# I2C_ESP32_Module.net
KiCad netlist of a schematic drawn in Altium Designer
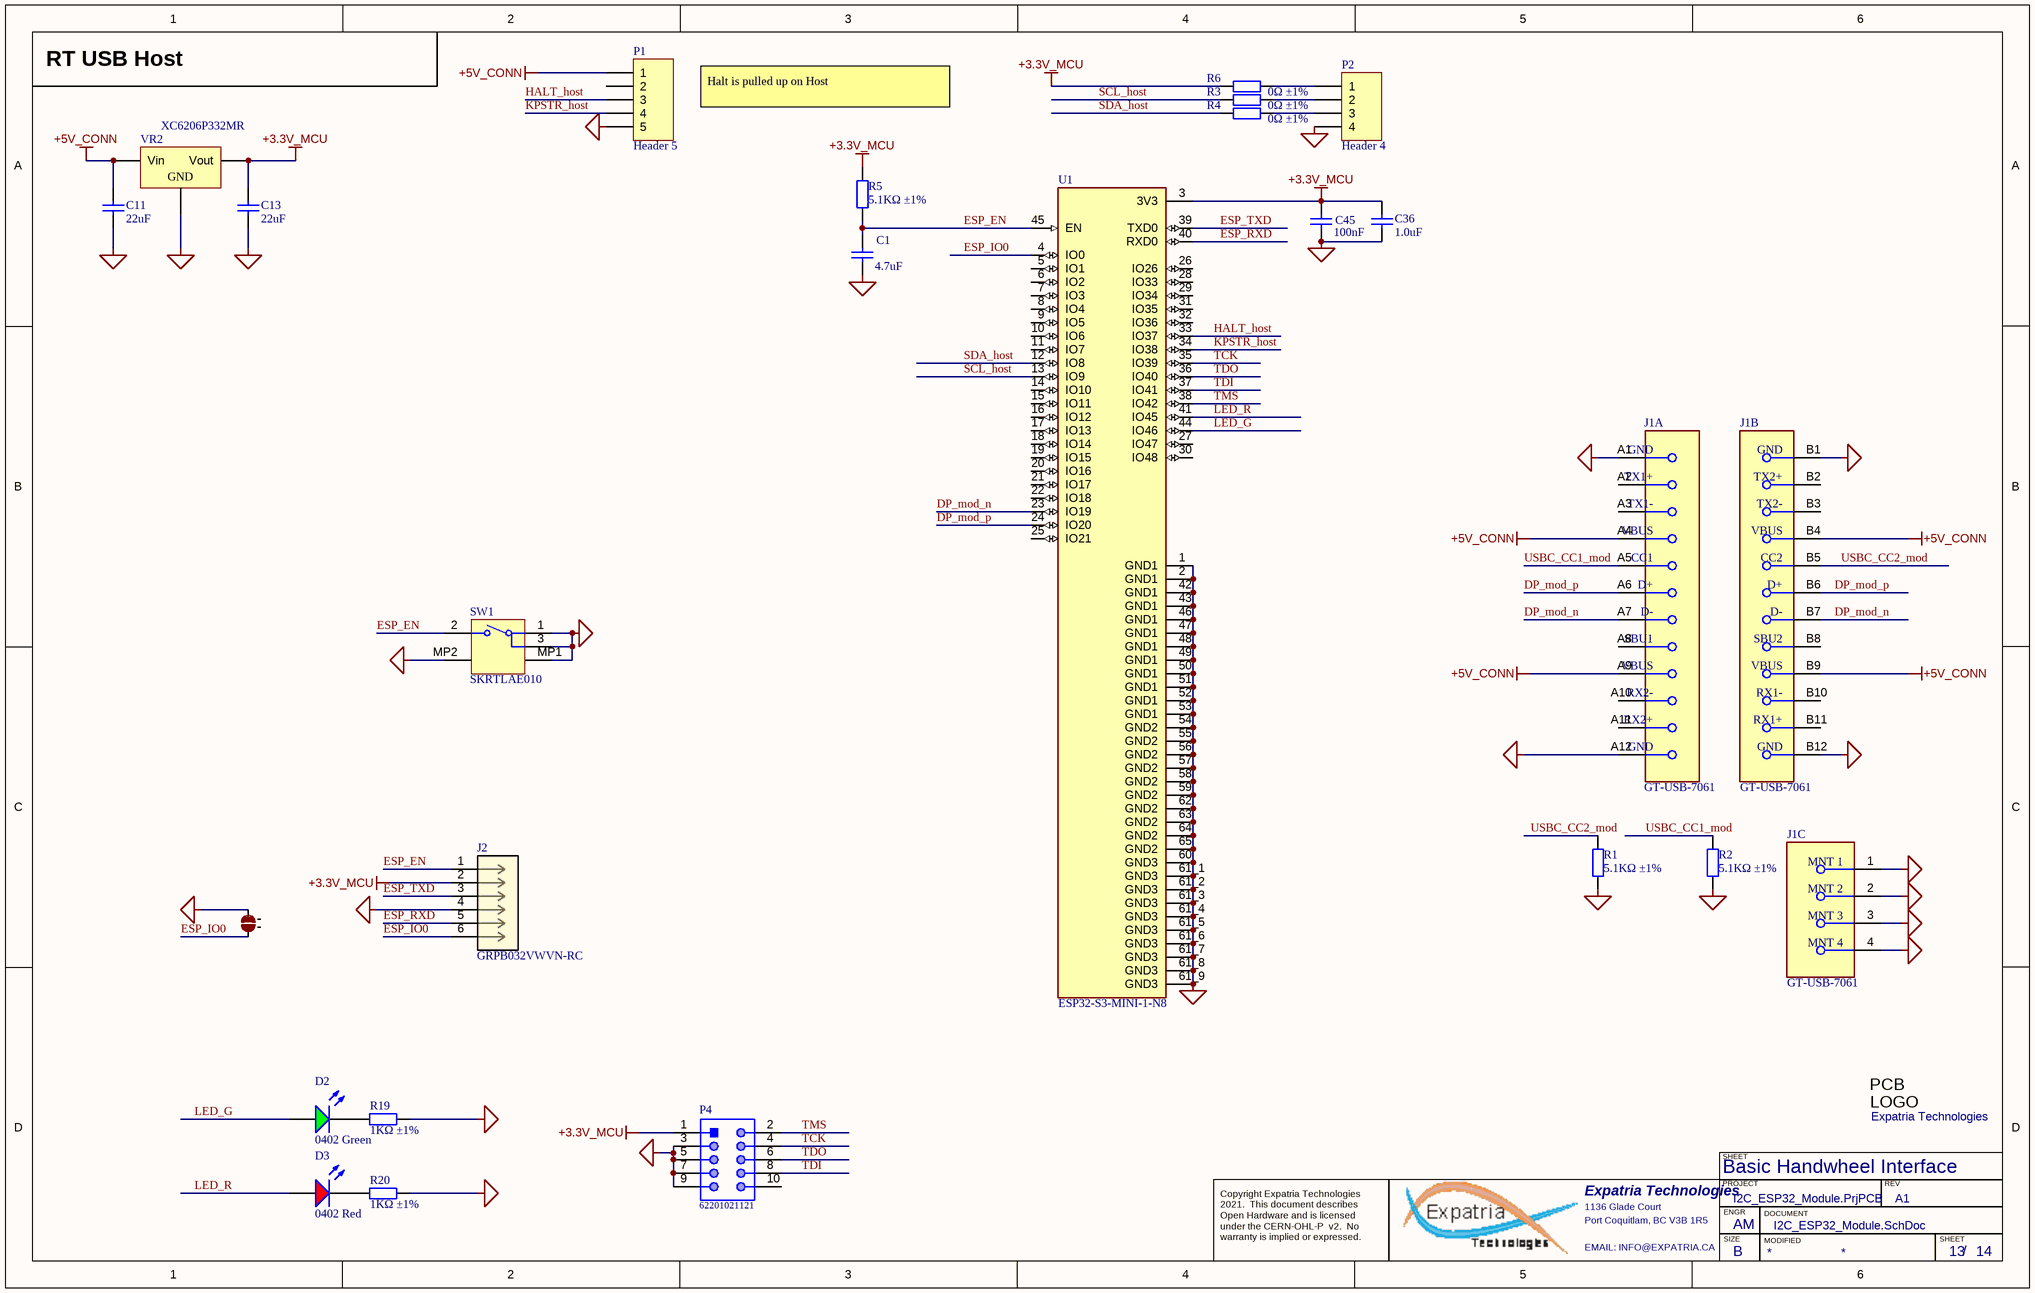
[diagram p0: I2C_ESP32_Module.SchDoc]

(export (version "E")
  (design (tool "Eeschema 10.0.6"))
  (components
    (comp (ref "C1")
      (value "4.7uF")
      (footprint "0402_C")
      (description "Chip capacitor")
      (fields
        (field (name "MANUFACTURER") "Samsung Electro-Mechanics")
        (field (name "PARTNUMBER") "CL05A475MP5NRNC")
      )
      (libsource (lib "Cap") (part "0402 4.7uF (475) 20% 10V"))
    )
    (comp (ref "C11")
      (value "22uF")
      (footprint "0603_C")
      (description "Chip capacitors")
      (fields
        (field (name "MANUFACTURER") "Samsung Electro-Mechanics")
        (field (name "PARTNUMBER") "CL10A226MQ8NRNC")
      )
      (libsource (lib "Cap") (part "0603 22uF (226) 20% 6.3V"))
    )
    (comp (ref "C13")
      (value "22uF")
      (footprint "0603_C")
      (description "Chip capacitors")
      (fields
        (field (name "MANUFACTURER") "Samsung Electro-Mechanics")
        (field (name "PARTNUMBER") "CL10A226MQ8NRNC")
      )
      (libsource (lib "Cap") (part "0603 22uF (226) 20% 6.3V"))
    )
    (comp (ref "C36")
      (value "1.0uF")
      (footprint "0402_C")
      (description "Chip capacitor")
      (fields
        (field (name "MANUFACTURER") "Samsung Electro-Mechanics")
        (field (name "PARTNUMBER") "CL05A105KA5NQNC")
      )
      (libsource (lib "Cap") (part "0402 1.0uF (105) 10% 25V"))
    )
    (comp (ref "C45")
      (value "100nF")
      (footprint "0402_C")
      (description "Chip capacitors")
      (fields
        (field (name "MANUFACTURER") "Samsung Electro-Mechanics")
        (field (name "PARTNUMBER") "CL05B104KO5NNNC")
      )
      (libsource (lib "Cap") (part "0402 100nF (104) 10% 16V"))
    )
    (comp (ref "D2")
      (value "0402 Green")
      (footprint "LED 0402_1005 RED")
      (description "LED")
      (libsource (lib "LED") (part "0402 LED Green"))
    )
    (comp (ref "D3")
      (value "0402 Red")
      (footprint "LED 0402_1005 RED")
      (description "LED")
      (libsource (lib "LED") (part "0402 LED Red"))
    )
    (comp (ref "J1")
      (value "GT-USB-7061")
      (footprint "USB-C-SMD_GT-USB-7061")
      (description "CONN RCP USB3.1 TYPEC 24P SMD VERT")
      (fields (field (name "MANUFACTURER") "G-Switch"))
      (libsource (lib "") (part "USBC-GT-USB-7061_1"))
    )
    (comp (ref "J2")
      (value "GRPB032VWVN-RC")
      (footprint "CONN6_GRPB032VWVN-RC_SUL")
      (description "Description")
      (fields (field (name "COPYRIGHT") "Copyright (C) 2025 Ultra Librarian. All rights reserved."))
      (libsource (lib "Miscellaneous Connectors") (part "GRPB032VWVN-RC"))
    )
    (comp (ref "J3")
      (value "2 way net solder junction - Normally Open")
      (footprint "2waySolder_NO")
      (libsource (lib "PrintNC_GRBLHAL_Breakout") (part "2waySolderNO"))
    )
    (comp (ref "Logo1")
      (value "Expatria Technologies")
      (footprint "Expatria-Logo")
      (libsource (lib "PrintNC_GRBLHAL_Breakout") (part "SBT-Logo"))
    )
    (comp (ref "P1")
      (value "Header 5")
      (footprint "HDR1X5")
      (description "Header, 5-Pin")
      (fields (field (name "PUBLISHER") "Altium Limited"))
      (libsource (lib "PrintNC_GRBLHAL_Breakout") (part "Header 5"))
    )
    (comp (ref "P2")
      (value "Header 4")
      (footprint "HDR1X4")
      (description "Header, 4-Pin")
      (fields (field (name "PUBLISHER") "Altium Limited"))
      (libsource (lib "PrintNC_GRBLHAL_Breakout") (part "Header 4"))
    )
    (comp (ref "P4")
      (value "62201021121")
      (footprint "62201021121")
      (description "THT Vertical Pin Header WR-PHD, Pitch 1.27 mm, Dual Row, 10 pins")
      (fields (field (name "MANUFACTURER") "Wurth Elektronik") (field (name "PUBLISHER") "WurthElektronik"))
      (libsource (lib "Altium Content Vault") (part "WE-CN-2P-M-R10"))
    )
    (comp (ref "R1")
      (value "5.1KΩ ±1%")
      (footprint "0402_R")
      (description "Chip resistor")
      (fields (field (name "MANUFACTURER") "Uniroyal Elec") (field (name "PARTNUMBER") "0402WGF5101TCE"))
      (libsource (lib "RES") (part "0402 5.1K (5101) 1%"))
    )
    (comp (ref "R2")
      (value "5.1KΩ ±1%")
      (footprint "0402_R")
      (description "Chip resistor")
      (fields (field (name "MANUFACTURER") "Uniroyal Elec") (field (name "PARTNUMBER") "0402WGF5101TCE"))
      (libsource (lib "RES") (part "0402 5.1K (5101) 1%"))
    )
    (comp (ref "R3")
      (value "0Ω ±1%")
      (footprint "0402_R")
      (description "Chip resistor")
      (fields (field (name "MANUFACTURER") "Uniroyal Elec") (field (name "PARTNUMBER") "0402WGF0000TCE"))
      (libsource (lib "RES") (part "0402 0R (0R0) 1%"))
    )
    (comp (ref "R4")
      (value "0Ω ±1%")
      (footprint "0402_R")
      (description "Chip resistor")
      (fields (field (name "MANUFACTURER") "Uniroyal Elec") (field (name "PARTNUMBER") "0402WGF0000TCE"))
      (libsource (lib "RES") (part "0402 0R (0R0) 1%"))
    )
    (comp (ref "R5")
      (value "5.1KΩ ±1%")
      (footprint "0402_R")
      (description "Chip resistor")
      (fields (field (name "MANUFACTURER") "Uniroyal Elec") (field (name "PARTNUMBER") "0402WGF5101TCE"))
      (libsource (lib "RES") (part "0402 5.1K (5101) 1%"))
    )
    (comp (ref "R6")
      (value "0Ω ±1%")
      (footprint "0402_R")
      (description "Chip resistor")
      (fields (field (name "MANUFACTURER") "Uniroyal Elec") (field (name "PARTNUMBER") "0402WGF0000TCE"))
      (libsource (lib "RES") (part "0402 0R (0R0) 1%"))
    )
    (comp (ref "R19")
      (value "1KΩ ±1%")
      (footprint "0402_R")
      (description "Chip resistor")
      (fields (field (name "MANUFACTURER") "Uniroyal Elec") (field (name "PARTNUMBER") "0402WGF1001TCE"))
      (libsource (lib "RES") (part "0402 1K (1001) 1%"))
    )
    (comp (ref "R20")
      (value "1KΩ ±1%")
      (footprint "0402_R")
      (description "Chip resistor")
      (fields (field (name "MANUFACTURER") "Uniroyal Elec") (field (name "PARTNUMBER") "0402WGF1001TCE"))
      (libsource (lib "RES") (part "0402 1K (1001) 1%"))
    )
    (comp (ref "SW1")
      (value "SKRTLAE010")
      (footprint "ALPS-SKRTLAE010_V")
      (description "Side Push Type, 250 V, -40 to 90 degC, 3-Pin SMD, RoHS, Tape and Reel")
      (fields (field (name "MANUFACTURER") "ALPS"))
      (libsource (lib "Altium Content Vault") (part "SW_SPST-3_A"))
    )
    (comp (ref "U1")
      (value "ESP32-S3-MINI-1-N8")
      (footprint "XCVR_ESP32-S3-MINI-1-N8")
      (description "Bluetooth, WiFi 802.11b/g/n, Bluetooth v5.0 Transceiver Module 2.4GHz Antenna")
      (fields (field (name "MF") "Espressif Systems"))
      (libsource (lib "Universal_CNC_Breakout") (part "ESP32-S3-MINI-1U-N8"))
    )
    (comp (ref "VR2")
      (value "XC6206P332MR")
      (footprint "SOT-23-3L")
      (description "200mA 680mV@(100mA) Fixed 3.3V~3.3V Positive 1 6V SOT-23-3L Linear Voltage Regulators (LDO) ROHS")
      (libsource (lib "LDO") (part "SOT-23 XC6206P332MR"))
    )
  )
  (nets
    (net (code "1") (name "+3.3V_MCU") (class "Default")
      (node (ref "C13") (pin "2") (pinfunction "2_2") (pintype "passive"))
      (node (ref "C36") (pin "2") (pinfunction "2_2") (pintype "passive"))
      (node (ref "C45") (pin "2") (pinfunction "2_2") (pintype "passive"))
      (node (ref "J2") (pin "2") (pinfunction "2_2") (pintype "passive"))
      (node (ref "P4") (pin "1") (pinfunction "1_1") (pintype "passive"))
      (node (ref "R5") (pin "1") (pinfunction "1_1") (pintype "passive"))
      (node (ref "R6") (pin "2") (pinfunction "2_2") (pintype "passive"))
      (node (ref "U1") (pin "3") (pinfunction "3V3_3") (pintype "power_in"))
      (node (ref "VR2") (pin "2") (pinfunction "Vout_2") (pintype "passive"))
    )
    (net (code "2") (name "+5V_CONN") (class "Default")
      (node (ref "C11") (pin "2") (pinfunction "2_2") (pintype "passive"))
      (node (ref "J1") (pin "A4") (pinfunction "VBUS_A4") (pintype "passive"))
      (node (ref "J1") (pin "A9") (pinfunction "VBUS_A9") (pintype "passive"))
      (node (ref "J1") (pin "B4") (pinfunction "VBUS_B4") (pintype "passive"))
      (node (ref "J1") (pin "B9") (pinfunction "VBUS_B9") (pintype "passive"))
      (node (ref "P1") (pin "1") (pinfunction "1_1") (pintype "passive"))
      (node (ref "VR2") (pin "3") (pinfunction "Vin_3") (pintype "passive"))
    )
    (net (code "3") (name "/DP_mod_n") (class "Default")
      (node (ref "J1") (pin "A7") (pinfunction "D-_A7") (pintype "passive"))
      (node (ref "J1") (pin "B7") (pinfunction "D-_B7") (pintype "passive"))
      (node (ref "U1") (pin "23") (pinfunction "IO19_23") (pintype "bidirectional"))
    )
    (net (code "4") (name "/DP_mod_p") (class "Default")
      (node (ref "J1") (pin "A6") (pinfunction "D+_A6") (pintype "passive"))
      (node (ref "J1") (pin "B6") (pinfunction "D+_B6") (pintype "passive"))
      (node (ref "U1") (pin "24") (pinfunction "IO20_24") (pintype "bidirectional"))
    )
    (net (code "5") (name "/ESP_EN") (class "Default")
      (node (ref "C1") (pin "2") (pinfunction "2_2") (pintype "passive"))
      (node (ref "J2") (pin "1") (pinfunction "1_1") (pintype "passive"))
      (node (ref "R5") (pin "2") (pinfunction "2_2") (pintype "passive"))
      (node (ref "SW1") (pin "2") (pinfunction "2_2") (pintype "passive"))
      (node (ref "U1") (pin "45") (pinfunction "EN_45") (pintype "input"))
    )
    (net (code "6") (name "/ESP_IO0") (class "Default")
      (node (ref "J2") (pin "6") (pinfunction "6_6") (pintype "passive"))
      (node (ref "J3") (pin "1") (pinfunction "1_1") (pintype "passive"))
      (node (ref "U1") (pin "4") (pinfunction "IO0_4") (pintype "bidirectional"))
    )
    (net (code "7") (name "/ESP_RXD") (class "Default")
      (node (ref "J2") (pin "5") (pinfunction "5_5") (pintype "passive"))
      (node (ref "U1") (pin "40") (pinfunction "RXD0_40") (pintype "bidirectional"))
    )
    (net (code "8") (name "/ESP_TXD") (class "Default")
      (node (ref "J2") (pin "3") (pinfunction "3_3") (pintype "passive"))
      (node (ref "U1") (pin "39") (pinfunction "TXD0_39") (pintype "bidirectional"))
    )
    (net (code "9") (name "/HALT_host") (class "Default")
      (node (ref "P1") (pin "3") (pinfunction "3_3") (pintype "passive"))
      (node (ref "U1") (pin "33") (pinfunction "IO37_33") (pintype "bidirectional"))
    )
    (net (code "10") (name "/KPSTR_host") (class "Default")
      (node (ref "P1") (pin "4") (pinfunction "4_4") (pintype "passive"))
      (node (ref "U1") (pin "34") (pinfunction "IO38_34") (pintype "bidirectional"))
    )
    (net (code "11") (name "/LED_G") (class "Default")
      (node (ref "D2") (pin "A") (pinfunction "A_A") (pintype "passive"))
      (node (ref "U1") (pin "44") (pinfunction "IO46_44") (pintype "bidirectional"))
    )
    (net (code "12") (name "/LED_R") (class "Default")
      (node (ref "D3") (pin "A") (pinfunction "A_A") (pintype "passive"))
      (node (ref "U1") (pin "41") (pinfunction "IO45_41") (pintype "bidirectional"))
    )
    (net (code "13") (name "/SCL_host") (class "Default")
      (node (ref "R3") (pin "2") (pinfunction "2_2") (pintype "passive"))
      (node (ref "U1") (pin "13") (pinfunction "IO9_13") (pintype "bidirectional"))
    )
    (net (code "14") (name "/SDA_host") (class "Default")
      (node (ref "R4") (pin "2") (pinfunction "2_2") (pintype "passive"))
      (node (ref "U1") (pin "12") (pinfunction "IO8_12") (pintype "bidirectional"))
    )
    (net (code "15") (name "/TCK") (class "Default")
      (node (ref "P4") (pin "4") (pinfunction "4_4") (pintype "passive"))
      (node (ref "U1") (pin "35") (pinfunction "IO39_35") (pintype "bidirectional"))
    )
    (net (code "16") (name "/TDI") (class "Default")
      (node (ref "P4") (pin "8") (pinfunction "8_8") (pintype "passive"))
      (node (ref "U1") (pin "37") (pinfunction "IO41_37") (pintype "bidirectional"))
    )
    (net (code "17") (name "/TDO") (class "Default")
      (node (ref "P4") (pin "6") (pinfunction "6_6") (pintype "passive"))
      (node (ref "U1") (pin "36") (pinfunction "IO40_36") (pintype "bidirectional"))
    )
    (net (code "18") (name "/TMS") (class "Default")
      (node (ref "P4") (pin "2") (pinfunction "2_2") (pintype "passive"))
      (node (ref "U1") (pin "38") (pinfunction "IO42_38") (pintype "bidirectional"))
    )
    (net (code "19") (name "/USBC_CC1_mod") (class "Default")
      (node (ref "J1") (pin "A5") (pinfunction "CC1_A5") (pintype "passive"))
      (node (ref "R2") (pin "1") (pinfunction "1_1") (pintype "passive"))
    )
    (net (code "20") (name "/USBC_CC2_mod") (class "Default")
      (node (ref "J1") (pin "B5") (pinfunction "CC2_B5") (pintype "passive"))
      (node (ref "R1") (pin "1") (pinfunction "1_1") (pintype "passive"))
    )
    (net (code "21") (name "GND") (class "Default")
      (node (ref "C1") (pin "1") (pinfunction "1_1") (pintype "passive"))
      (node (ref "C11") (pin "1") (pinfunction "1_1") (pintype "passive"))
      (node (ref "C13") (pin "1") (pinfunction "1_1") (pintype "passive"))
      (node (ref "C36") (pin "1") (pinfunction "1_1") (pintype "passive"))
      (node (ref "C45") (pin "1") (pinfunction "1_1") (pintype "passive"))
      (node (ref "J1") (pin "1") (pinfunction "MNT_1_1") (pintype "passive"))
      (node (ref "J1") (pin "2") (pinfunction "MNT_2_2") (pintype "passive"))
      (node (ref "J1") (pin "3") (pinfunction "MNT_3_3") (pintype "passive"))
      (node (ref "J1") (pin "4") (pinfunction "MNT_4_4") (pintype "passive"))
      (node (ref "J1") (pin "A1") (pinfunction "GND_A1") (pintype "passive"))
      (node (ref "J1") (pin "A12") (pinfunction "GND_A12") (pintype "passive"))
      (node (ref "J1") (pin "B1") (pinfunction "GND_B1") (pintype "passive"))
      (node (ref "J1") (pin "B12") (pinfunction "GND_B12") (pintype "passive"))
      (node (ref "J2") (pin "4") (pinfunction "4_4") (pintype "passive"))
      (node (ref "J3") (pin "2") (pinfunction "2_2") (pintype "passive"))
      (node (ref "P1") (pin "5") (pinfunction "5_5") (pintype "passive"))
      (node (ref "P2") (pin "4") (pinfunction "4_4") (pintype "passive"))
      (node (ref "P4") (pin "3") (pinfunction "3_3") (pintype "passive"))
      (node (ref "P4") (pin "5") (pinfunction "5_5") (pintype "passive"))
      (node (ref "P4") (pin "7") (pinfunction "7_7") (pintype "passive"))
      (node (ref "P4") (pin "9") (pinfunction "9_9") (pintype "passive"))
      (node (ref "R1") (pin "2") (pinfunction "2_2") (pintype "passive"))
      (node (ref "R19") (pin "2") (pinfunction "2_2") (pintype "passive"))
      (node (ref "R2") (pin "2") (pinfunction "2_2") (pintype "passive"))
      (node (ref "R20") (pin "2") (pinfunction "2_2") (pintype "passive"))
      (node (ref "SW1") (pin "1") (pinfunction "1_1") (pintype "passive"))
      (node (ref "SW1") (pin "3") (pinfunction "3_3") (pintype "passive"))
      (node (ref "SW1") (pin "MP1") (pinfunction "MP1_MP1") (pintype "passive"))
      (node (ref "SW1") (pin "MP2") (pinfunction "MP2_MP2") (pintype "passive"))
      (node (ref "U1") (pin "1") (pinfunction "GND1_1") (pintype "power_in"))
      (node (ref "U1") (pin "2") (pinfunction "GND1_2") (pintype "power_in"))
      (node (ref "U1") (pin "42") (pinfunction "GND1_42") (pintype "power_in"))
      (node (ref "U1") (pin "43") (pinfunction "GND1_43") (pintype "power_in"))
      (node (ref "U1") (pin "46") (pinfunction "GND1_46") (pintype "power_in"))
      (node (ref "U1") (pin "47") (pinfunction "GND1_47") (pintype "power_in"))
      (node (ref "U1") (pin "48") (pinfunction "GND1_48") (pintype "power_in"))
      (node (ref "U1") (pin "49") (pinfunction "GND1_49") (pintype "power_in"))
      (node (ref "U1") (pin "50") (pinfunction "GND1_50") (pintype "power_in"))
      (node (ref "U1") (pin "51") (pinfunction "GND1_51") (pintype "power_in"))
      (node (ref "U1") (pin "52") (pinfunction "GND1_52") (pintype "power_in"))
      (node (ref "U1") (pin "53") (pinfunction "GND1_53") (pintype "power_in"))
      (node (ref "U1") (pin "54") (pinfunction "GND2_54") (pintype "power_in"))
      (node (ref "U1") (pin "55") (pinfunction "GND2_55") (pintype "power_in"))
      (node (ref "U1") (pin "56") (pinfunction "GND2_56") (pintype "power_in"))
      (node (ref "U1") (pin "57") (pinfunction "GND2_57") (pintype "power_in"))
      (node (ref "U1") (pin "58") (pinfunction "GND2_58") (pintype "power_in"))
      (node (ref "U1") (pin "59") (pinfunction "GND2_59") (pintype "power_in"))
      (node (ref "U1") (pin "60") (pinfunction "GND3_60") (pintype "power_in"))
      (node (ref "U1") (pin "61_1") (pinfunction "GND3_61_1") (pintype "power_in"))
      (node (ref "U1") (pin "61_2") (pinfunction "GND3_61_2") (pintype "power_in"))
      (node (ref "U1") (pin "61_3") (pinfunction "GND3_61_3") (pintype "power_in"))
      (node (ref "U1") (pin "61_4") (pinfunction "GND3_61_4") (pintype "power_in"))
      (node (ref "U1") (pin "61_5") (pinfunction "GND3_61_5") (pintype "power_in"))
      (node (ref "U1") (pin "61_6") (pinfunction "GND3_61_6") (pintype "power_in"))
      (node (ref "U1") (pin "61_7") (pinfunction "GND3_61_7") (pintype "power_in"))
      (node (ref "U1") (pin "61_8") (pinfunction "GND3_61_8") (pintype "power_in"))
      (node (ref "U1") (pin "61_9") (pinfunction "GND3_61_9") (pintype "power_in"))
      (node (ref "U1") (pin "62") (pinfunction "GND2_62") (pintype "power_in"))
      (node (ref "U1") (pin "63") (pinfunction "GND2_63") (pintype "power_in"))
      (node (ref "U1") (pin "64") (pinfunction "GND2_64") (pintype "power_in"))
      (node (ref "U1") (pin "65") (pinfunction "GND2_65") (pintype "power_in"))
      (node (ref "VR2") (pin "1") (pinfunction "GND_1") (pintype "passive"))
    )
    (net (code "22") (name "Net-(D2-PadK)") (class "Default")
      (node (ref "D2") (pin "K") (pinfunction "K_K") (pintype "passive"))
      (node (ref "R19") (pin "1") (pinfunction "1_1") (pintype "passive"))
    )
    (net (code "23") (name "Net-(D3-PadK)") (class "Default")
      (node (ref "D3") (pin "K") (pinfunction "K_K") (pintype "passive"))
      (node (ref "R20") (pin "1") (pinfunction "1_1") (pintype "passive"))
    )
    (net (code "24") (name "Net-(P2-Pad1)") (class "Default")
      (node (ref "P2") (pin "1") (pinfunction "1_1") (pintype "passive"))
      (node (ref "R6") (pin "1") (pinfunction "1_1") (pintype "passive"))
    )
    (net (code "25") (name "Net-(P2-Pad2)") (class "Default")
      (node (ref "P2") (pin "2") (pinfunction "2_2") (pintype "passive"))
      (node (ref "R3") (pin "1") (pinfunction "1_1") (pintype "passive"))
    )
    (net (code "26") (name "Net-(P2-Pad3)") (class "Default")
      (node (ref "P2") (pin "3") (pinfunction "3_3") (pintype "passive"))
      (node (ref "R4") (pin "1") (pinfunction "1_1") (pintype "passive"))
    )
    (net (code "27") (name "unconnected-(J1A-RX2+-PadA11)") (class "Default")
      (node (ref "J1") (pin "A11") (pinfunction "RX2+_A11") (pintype "passive"))
    )
    (net (code "28") (name "unconnected-(J1A-RX2--PadA10)") (class "Default")
      (node (ref "J1") (pin "A10") (pinfunction "RX2-_A10") (pintype "passive"))
    )
    (net (code "29") (name "unconnected-(J1A-SBU1-PadA8)") (class "Default")
      (node (ref "J1") (pin "A8") (pinfunction "SBU1_A8") (pintype "passive"))
    )
    (net (code "30") (name "unconnected-(J1A-TX1+-PadA2)") (class "Default")
      (node (ref "J1") (pin "A2") (pinfunction "TX1+_A2") (pintype "passive"))
    )
    (net (code "31") (name "unconnected-(J1A-TX1--PadA3)") (class "Default")
      (node (ref "J1") (pin "A3") (pinfunction "TX1-_A3") (pintype "passive"))
    )
    (net (code "32") (name "unconnected-(J1B-RX1+-PadB11)") (class "Default")
      (node (ref "J1") (pin "B11") (pinfunction "RX1+_B11") (pintype "passive"))
    )
    (net (code "33") (name "unconnected-(J1B-RX1--PadB10)") (class "Default")
      (node (ref "J1") (pin "B10") (pinfunction "RX1-_B10") (pintype "passive"))
    )
    (net (code "34") (name "unconnected-(J1B-SBU2-PadB8)") (class "Default")
      (node (ref "J1") (pin "B8") (pinfunction "SBU2_B8") (pintype "passive"))
    )
    (net (code "35") (name "unconnected-(J1B-TX2+-PadB2)") (class "Default")
      (node (ref "J1") (pin "B2") (pinfunction "TX2+_B2") (pintype "passive"))
    )
    (net (code "36") (name "unconnected-(J1B-TX2--PadB3)") (class "Default")
      (node (ref "J1") (pin "B3") (pinfunction "TX2-_B3") (pintype "passive"))
    )
    (net (code "37") (name "unconnected-(P1-Pad2)") (class "Default")
      (node (ref "P1") (pin "2") (pinfunction "2_2") (pintype "passive"))
    )
    (net (code "38") (name "unconnected-(P4-Pad10)") (class "Default")
      (node (ref "P4") (pin "10") (pinfunction "10_10") (pintype "passive"))
    )
    (net (code "39") (name "unconnected-(U1-IO1-Pad5)") (class "Default")
      (node (ref "U1") (pin "5") (pinfunction "IO1_5") (pintype "bidirectional"))
    )
    (net (code "40") (name "unconnected-(U1-IO2-Pad6)") (class "Default")
      (node (ref "U1") (pin "6") (pinfunction "IO2_6") (pintype "bidirectional"))
    )
    (net (code "41") (name "unconnected-(U1-IO3-Pad7)") (class "Default")
      (node (ref "U1") (pin "7") (pinfunction "IO3_7") (pintype "bidirectional"))
    )
    (net (code "42") (name "unconnected-(U1-IO4-Pad8)") (class "Default")
      (node (ref "U1") (pin "8") (pinfunction "IO4_8") (pintype "bidirectional"))
    )
    (net (code "43") (name "unconnected-(U1-IO5-Pad9)") (class "Default")
      (node (ref "U1") (pin "9") (pinfunction "IO5_9") (pintype "bidirectional"))
    )
    (net (code "44") (name "unconnected-(U1-IO6-Pad10)") (class "Default")
      (node (ref "U1") (pin "10") (pinfunction "IO6_10") (pintype "bidirectional"))
    )
    (net (code "45") (name "unconnected-(U1-IO7-Pad11)") (class "Default")
      (node (ref "U1") (pin "11") (pinfunction "IO7_11") (pintype "bidirectional"))
    )
    (net (code "46") (name "unconnected-(U1-IO10-Pad14)") (class "Default")
      (node (ref "U1") (pin "14") (pinfunction "IO10_14") (pintype "bidirectional"))
    )
    (net (code "47") (name "unconnected-(U1-IO11-Pad15)") (class "Default")
      (node (ref "U1") (pin "15") (pinfunction "IO11_15") (pintype "bidirectional"))
    )
    (net (code "48") (name "unconnected-(U1-IO12-Pad16)") (class "Default")
      (node (ref "U1") (pin "16") (pinfunction "IO12_16") (pintype "bidirectional"))
    )
    (net (code "49") (name "unconnected-(U1-IO13-Pad17)") (class "Default")
      (node (ref "U1") (pin "17") (pinfunction "IO13_17") (pintype "bidirectional"))
    )
    (net (code "50") (name "unconnected-(U1-IO14-Pad18)") (class "Default")
      (node (ref "U1") (pin "18") (pinfunction "IO14_18") (pintype "bidirectional"))
    )
    (net (code "51") (name "unconnected-(U1-IO15-Pad19)") (class "Default")
      (node (ref "U1") (pin "19") (pinfunction "IO15_19") (pintype "bidirectional"))
    )
    (net (code "52") (name "unconnected-(U1-IO16-Pad20)") (class "Default")
      (node (ref "U1") (pin "20") (pinfunction "IO16_20") (pintype "bidirectional"))
    )
    (net (code "53") (name "unconnected-(U1-IO17-Pad21)") (class "Default")
      (node (ref "U1") (pin "21") (pinfunction "IO17_21") (pintype "bidirectional"))
    )
    (net (code "54") (name "unconnected-(U1-IO18-Pad22)") (class "Default")
      (node (ref "U1") (pin "22") (pinfunction "IO18_22") (pintype "bidirectional"))
    )
    (net (code "55") (name "unconnected-(U1-IO21-Pad25)") (class "Default")
      (node (ref "U1") (pin "25") (pinfunction "IO21_25") (pintype "bidirectional"))
    )
    (net (code "56") (name "unconnected-(U1-IO26-Pad26)") (class "Default")
      (node (ref "U1") (pin "26") (pinfunction "IO26_26") (pintype "bidirectional"))
    )
    (net (code "57") (name "unconnected-(U1-IO33-Pad28)") (class "Default")
      (node (ref "U1") (pin "28") (pinfunction "IO33_28") (pintype "bidirectional"))
    )
    (net (code "58") (name "unconnected-(U1-IO34-Pad29)") (class "Default")
      (node (ref "U1") (pin "29") (pinfunction "IO34_29") (pintype "bidirectional"))
    )
    (net (code "59") (name "unconnected-(U1-IO35-Pad31)") (class "Default")
      (node (ref "U1") (pin "31") (pinfunction "IO35_31") (pintype "bidirectional"))
    )
    (net (code "60") (name "unconnected-(U1-IO36-Pad32)") (class "Default")
      (node (ref "U1") (pin "32") (pinfunction "IO36_32") (pintype "bidirectional"))
    )
    (net (code "61") (name "unconnected-(U1-IO47-Pad27)") (class "Default")
      (node (ref "U1") (pin "27") (pinfunction "IO47_27") (pintype "bidirectional"))
    )
    (net (code "62") (name "unconnected-(U1-IO48-Pad30)") (class "Default")
      (node (ref "U1") (pin "30") (pinfunction "IO48_30") (pintype "bidirectional"))
    )
  )
)
